# Analog_Drum.net
KiCad netlist of a schematic drawn in EAGLE
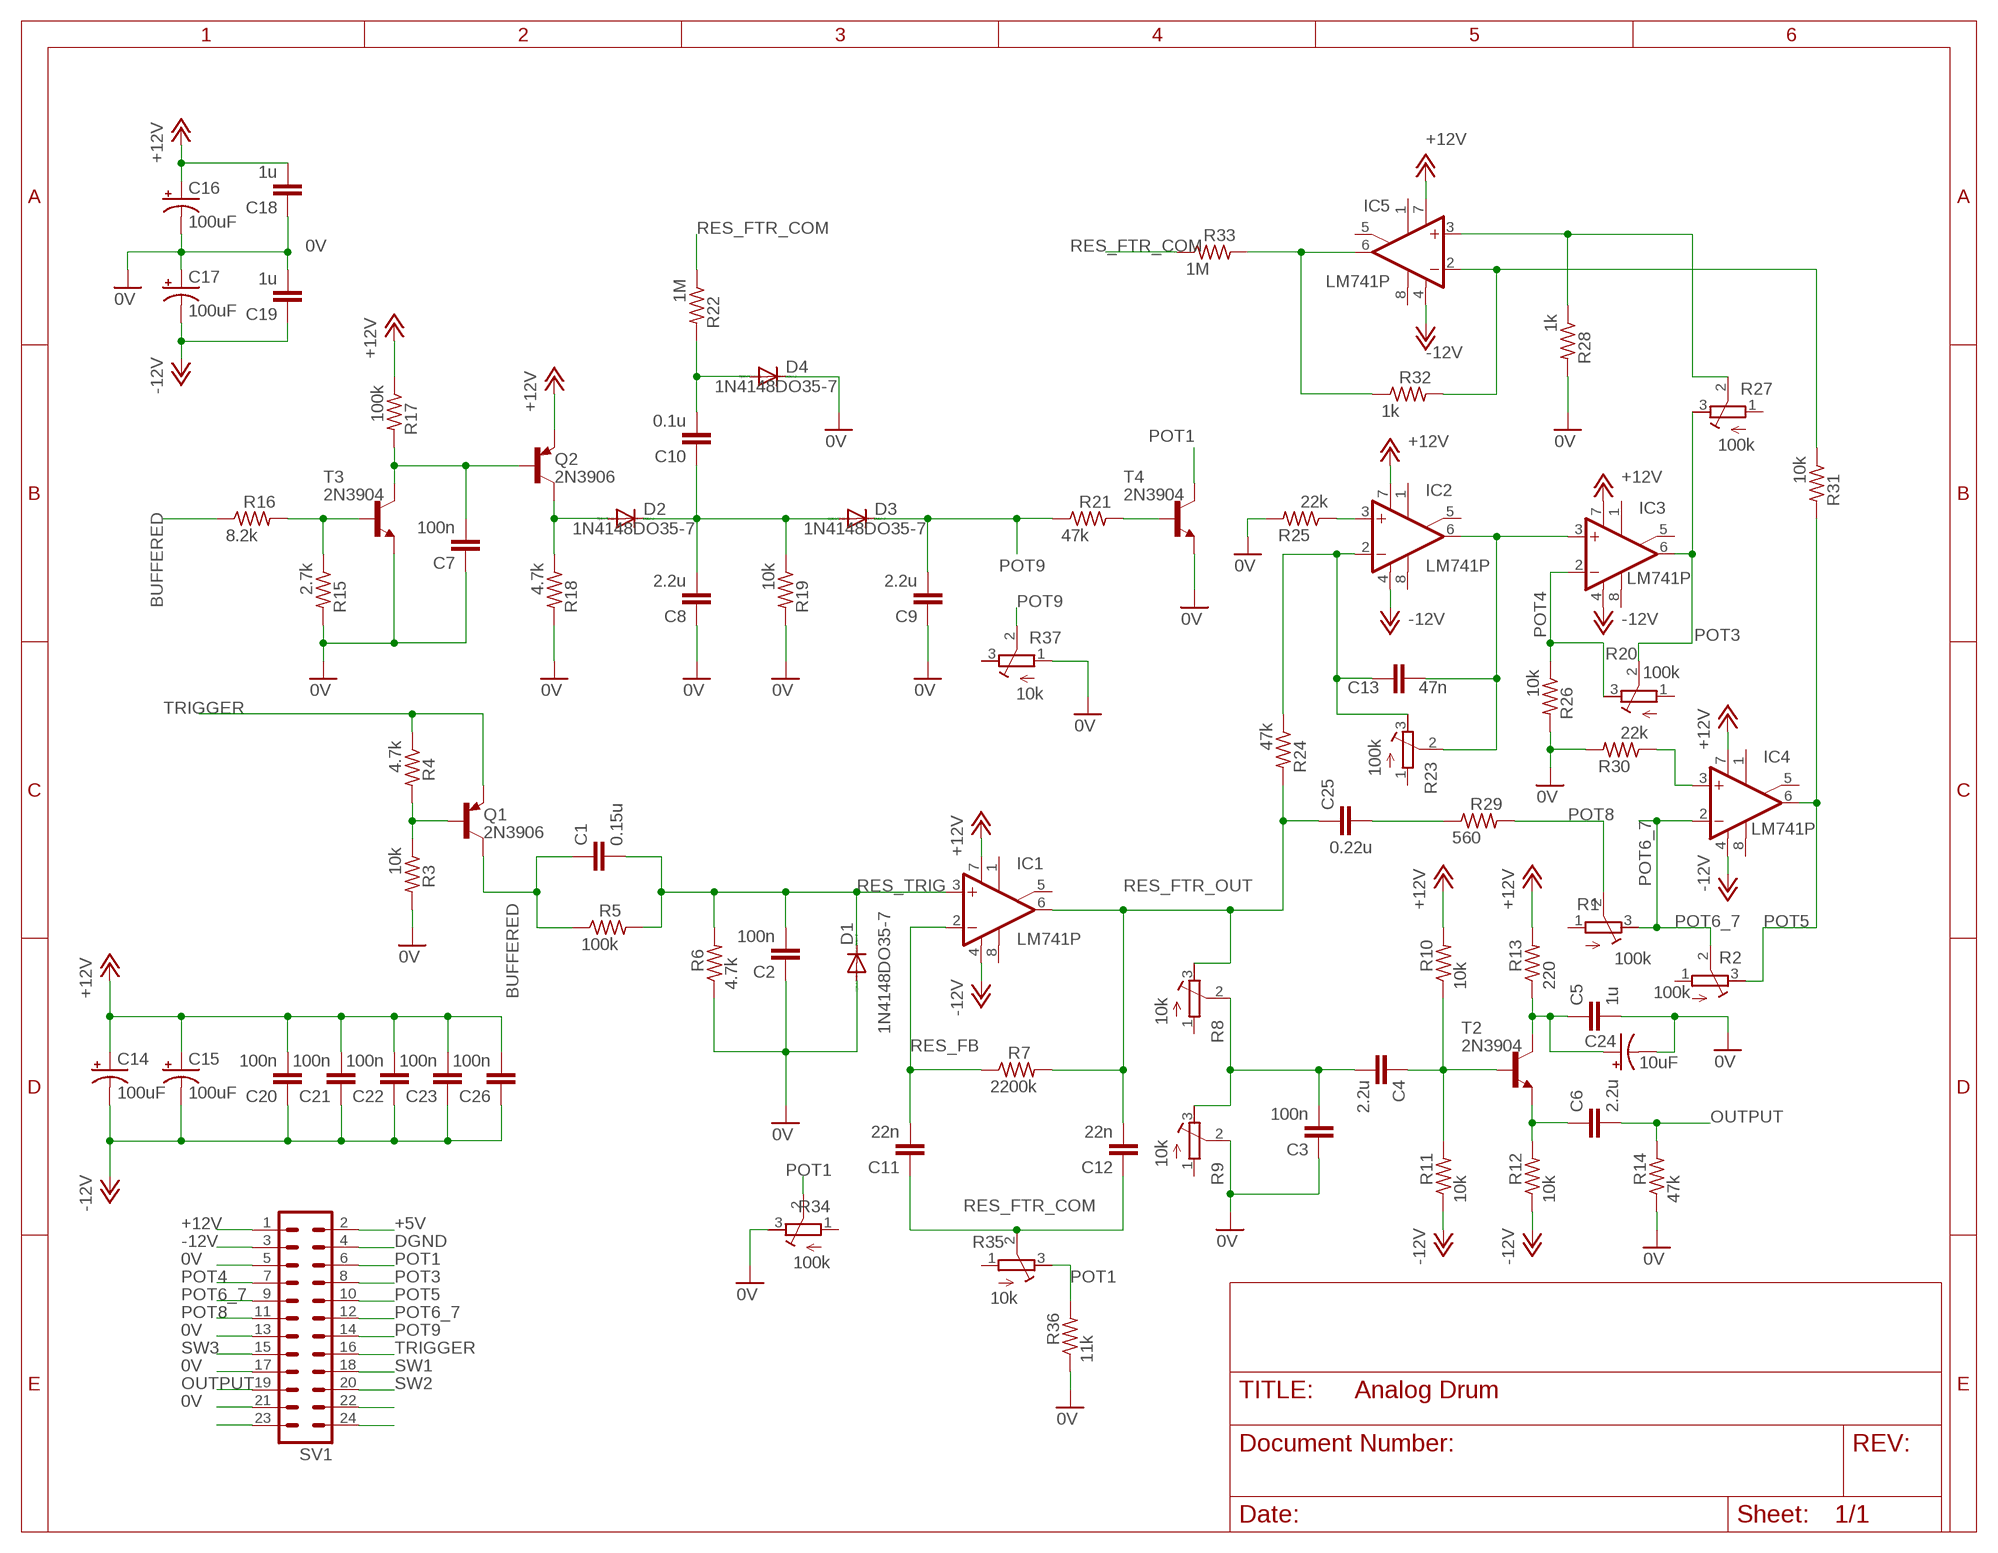
[diagram p0: schematic, sheet 1]

(export (version "E")
  (design (tool "Eeschema 10.0.6"))
  (components
    (comp (ref "C1")
      (value "0.15u")
      (footprint "eagle-import:C050-024X044")
      (libsource (lib "eagle-import") (part "C-EU050-024X044"))
    )
    (comp (ref "C2")
      (value "100n")
      (footprint "eagle-import:C050-024X044")
      (libsource (lib "eagle-import") (part "C-EU050-024X044"))
    )
    (comp (ref "C3")
      (value "100n")
      (footprint "eagle-import:C050-024X044")
      (libsource (lib "eagle-import") (part "C-EU050-024X044"))
    )
    (comp (ref "C4")
      (value "2.2u")
      (footprint "eagle-import:C050-024X044")
      (libsource (lib "eagle-import") (part "C-EU050-024X044"))
    )
    (comp (ref "C5")
      (value "1u")
      (footprint "eagle-import:C050-024X044")
      (libsource (lib "eagle-import") (part "C-EU050-024X044"))
    )
    (comp (ref "C6")
      (value "2.2u")
      (footprint "eagle-import:C050-024X044")
      (libsource (lib "eagle-import") (part "C-EU050-024X044"))
    )
    (comp (ref "C7")
      (value "100n")
      (footprint "eagle-import:C050-024X044")
      (libsource (lib "eagle-import") (part "C-EU050-024X044"))
    )
    (comp (ref "C8")
      (value "2.2u")
      (footprint "eagle-import:C050-024X044")
      (libsource (lib "eagle-import") (part "C-EU050-024X044"))
    )
    (comp (ref "C9")
      (value "2.2u")
      (footprint "eagle-import:C050-024X044")
      (libsource (lib "eagle-import") (part "C-EU050-024X044"))
    )
    (comp (ref "C10")
      (value "0.1u")
      (footprint "eagle-import:C050-024X044")
      (libsource (lib "eagle-import") (part "C-EU050-024X044"))
    )
    (comp (ref "C11")
      (value "22n")
      (footprint "eagle-import:C050-024X044")
      (libsource (lib "eagle-import") (part "C-EU050-024X044"))
    )
    (comp (ref "C12")
      (value "22n")
      (footprint "eagle-import:C050-024X044")
      (libsource (lib "eagle-import") (part "C-EU050-024X044"))
    )
    (comp (ref "C13")
      (value "47n")
      (footprint "eagle-import:C050-024X044")
      (libsource (lib "eagle-import") (part "C-EU050-024X044"))
    )
    (comp (ref "C14")
      (value "100uF")
      (footprint "eagle-import:E5-8,5")
      (libsource (lib "eagle-import") (part "CPOL-USE5-8.5"))
    )
    (comp (ref "C15")
      (value "100uF")
      (footprint "eagle-import:E5-8,5")
      (libsource (lib "eagle-import") (part "CPOL-USE5-8.5"))
    )
    (comp (ref "C16")
      (value "100uF")
      (footprint "eagle-import:E5-8,5")
      (libsource (lib "eagle-import") (part "CPOL-USE5-8.5"))
    )
    (comp (ref "C17")
      (value "100uF")
      (footprint "eagle-import:E5-8,5")
      (libsource (lib "eagle-import") (part "CPOL-USE5-8.5"))
    )
    (comp (ref "C18")
      (value "1u")
      (footprint "eagle-import:C050-024X044")
      (libsource (lib "eagle-import") (part "C-EU050-024X044"))
    )
    (comp (ref "C19")
      (value "1u")
      (footprint "eagle-import:C050-024X044")
      (libsource (lib "eagle-import") (part "C-EU050-024X044"))
    )
    (comp (ref "C20")
      (value "100n")
      (footprint "eagle-import:C050-024X044")
      (libsource (lib "eagle-import") (part "C-EU050-024X044"))
    )
    (comp (ref "C21")
      (value "100n")
      (footprint "eagle-import:C050-024X044")
      (libsource (lib "eagle-import") (part "C-EU050-024X044"))
    )
    (comp (ref "C22")
      (value "100n")
      (footprint "eagle-import:C050-024X044")
      (libsource (lib "eagle-import") (part "C-EU050-024X044"))
    )
    (comp (ref "C23")
      (value "100n")
      (footprint "eagle-import:C050-024X044")
      (libsource (lib "eagle-import") (part "C-EU050-024X044"))
    )
    (comp (ref "C24")
      (value "10uF")
      (footprint "eagle-import:E2,5-6")
      (libsource (lib "eagle-import") (part "CPOL-USE2.5-6"))
    )
    (comp (ref "C25")
      (value "0.22u")
      (footprint "eagle-import:C050-024X044")
      (libsource (lib "eagle-import") (part "C-EU050-024X044"))
    )
    (comp (ref "C26")
      (value "100n")
      (footprint "eagle-import:C050-024X044")
      (libsource (lib "eagle-import") (part "C-EU050-024X044"))
    )
    (comp (ref "D1")
      (value "1N4148DO35-7")
      (footprint "eagle-import:DO35-7")
      (libsource (lib "eagle-import") (part "1N4148DO35-7"))
    )
    (comp (ref "D2")
      (value "1N4148DO35-7")
      (footprint "eagle-import:DO35-7")
      (libsource (lib "eagle-import") (part "1N4148DO35-7"))
    )
    (comp (ref "D3")
      (value "1N4148DO35-7")
      (footprint "eagle-import:DO35-7")
      (libsource (lib "eagle-import") (part "1N4148DO35-7"))
    )
    (comp (ref "D4")
      (value "1N4148DO35-7")
      (footprint "eagle-import:DO35-7")
      (libsource (lib "eagle-import") (part "1N4148DO35-7"))
    )
    (comp (ref "IC1")
      (value "LM741P")
      (footprint "eagle-import:DIL08")
      (libsource (lib "eagle-import") (part "741PLM"))
    )
    (comp (ref "IC2")
      (value "LM741P")
      (footprint "eagle-import:DIL08")
      (libsource (lib "eagle-import") (part "741PLM"))
    )
    (comp (ref "IC3")
      (value "LM741P")
      (footprint "eagle-import:DIL08")
      (libsource (lib "eagle-import") (part "741PLM"))
    )
    (comp (ref "IC4")
      (value "LM741P")
      (footprint "eagle-import:DIL08")
      (libsource (lib "eagle-import") (part "741PLM"))
    )
    (comp (ref "IC5")
      (value "LM741P")
      (footprint "eagle-import:DIL08")
      (libsource (lib "eagle-import") (part "741PLM"))
    )
    (comp (ref "Q1")
      (value "2N3906")
      (footprint "eagle-import:TO92")
      (libsource (lib "eagle-import") (part "2N3906"))
    )
    (comp (ref "Q2")
      (value "2N3906")
      (footprint "eagle-import:TO92")
      (libsource (lib "eagle-import") (part "2N3906"))
    )
    (comp (ref "R1")
      (value "100k")
      (footprint "eagle-import:RTRIM64W")
      (libsource (lib "eagle-import") (part "R-TRIMM64W"))
    )
    (comp (ref "R2")
      (value "100k")
      (footprint "eagle-import:RTRIM64W")
      (libsource (lib "eagle-import") (part "R-TRIMM64W"))
    )
    (comp (ref "R3")
      (value "10k")
      (footprint "eagle-import:0207_10")
      (libsource (lib "eagle-import") (part "R-US_0207/10"))
    )
    (comp (ref "R4")
      (value "4.7k")
      (footprint "eagle-import:0207_10")
      (libsource (lib "eagle-import") (part "R-US_0207/10"))
    )
    (comp (ref "R5")
      (value "100k")
      (footprint "eagle-import:0207_10")
      (libsource (lib "eagle-import") (part "R-US_0207/10"))
    )
    (comp (ref "R6")
      (value "4.7k")
      (footprint "eagle-import:0207_10")
      (libsource (lib "eagle-import") (part "R-US_0207/10"))
    )
    (comp (ref "R7")
      (value "2200k")
      (footprint "eagle-import:0207_10")
      (libsource (lib "eagle-import") (part "R-US_0207/10"))
    )
    (comp (ref "R8")
      (value "10k")
      (footprint "eagle-import:RTRIM64W")
      (libsource (lib "eagle-import") (part "R-TRIMM64W"))
    )
    (comp (ref "R9")
      (value "10k")
      (footprint "eagle-import:RTRIM64W")
      (libsource (lib "eagle-import") (part "R-TRIMM64W"))
    )
    (comp (ref "R10")
      (value "10k")
      (footprint "eagle-import:0207_10")
      (libsource (lib "eagle-import") (part "R-US_0207/10"))
    )
    (comp (ref "R11")
      (value "10k")
      (footprint "eagle-import:0207_10")
      (libsource (lib "eagle-import") (part "R-US_0207/10"))
    )
    (comp (ref "R12")
      (value "10k")
      (footprint "eagle-import:0207_10")
      (libsource (lib "eagle-import") (part "R-US_0207/10"))
    )
    (comp (ref "R13")
      (value "220")
      (footprint "eagle-import:0207_10")
      (libsource (lib "eagle-import") (part "R-US_0207/10"))
    )
    (comp (ref "R14")
      (value "47k")
      (footprint "eagle-import:0207_10")
      (libsource (lib "eagle-import") (part "R-US_0207/10"))
    )
    (comp (ref "R15")
      (value "2.7k")
      (footprint "eagle-import:0207_10")
      (libsource (lib "eagle-import") (part "R-US_0207/10"))
    )
    (comp (ref "R16")
      (value "8.2k")
      (footprint "eagle-import:0207_10")
      (libsource (lib "eagle-import") (part "R-US_0207/10"))
    )
    (comp (ref "R17")
      (value "100k")
      (footprint "eagle-import:0207_10")
      (libsource (lib "eagle-import") (part "R-US_0207/10"))
    )
    (comp (ref "R18")
      (value "4.7k")
      (footprint "eagle-import:0207_10")
      (libsource (lib "eagle-import") (part "R-US_0207/10"))
    )
    (comp (ref "R19")
      (value "10k")
      (footprint "eagle-import:0207_10")
      (libsource (lib "eagle-import") (part "R-US_0207/10"))
    )
    (comp (ref "R20")
      (value "100k")
      (footprint "eagle-import:RTRIM64W")
      (libsource (lib "eagle-import") (part "R-TRIMM64W"))
    )
    (comp (ref "R21")
      (value "47k")
      (footprint "eagle-import:0207_10")
      (libsource (lib "eagle-import") (part "R-US_0207/10"))
    )
    (comp (ref "R22")
      (value "1M")
      (footprint "eagle-import:0207_10")
      (libsource (lib "eagle-import") (part "R-US_0207/10"))
    )
    (comp (ref "R23")
      (value "100k")
      (footprint "eagle-import:RTRIM64W")
      (libsource (lib "eagle-import") (part "R-TRIMM64W"))
    )
    (comp (ref "R24")
      (value "47k")
      (footprint "eagle-import:0207_10")
      (libsource (lib "eagle-import") (part "R-US_0207/10"))
    )
    (comp (ref "R25")
      (value "22k")
      (footprint "eagle-import:0207_10")
      (libsource (lib "eagle-import") (part "R-US_0207/10"))
    )
    (comp (ref "R26")
      (value "10k")
      (footprint "eagle-import:0207_10")
      (libsource (lib "eagle-import") (part "R-US_0207/10"))
    )
    (comp (ref "R27")
      (value "100k")
      (footprint "eagle-import:RTRIM64W")
      (libsource (lib "eagle-import") (part "R-TRIMM64W"))
    )
    (comp (ref "R28")
      (value "1k")
      (footprint "eagle-import:0207_10")
      (libsource (lib "eagle-import") (part "R-US_0207/10"))
    )
    (comp (ref "R29")
      (value "560")
      (footprint "eagle-import:0207_10")
      (libsource (lib "eagle-import") (part "R-US_0207/10"))
    )
    (comp (ref "R30")
      (value "22k")
      (footprint "eagle-import:0207_10")
      (libsource (lib "eagle-import") (part "R-US_0207/10"))
    )
    (comp (ref "R31")
      (value "10k")
      (footprint "eagle-import:0207_10")
      (libsource (lib "eagle-import") (part "R-US_0207/10"))
    )
    (comp (ref "R32")
      (value "1k")
      (footprint "eagle-import:0207_10")
      (libsource (lib "eagle-import") (part "R-US_0207/10"))
    )
    (comp (ref "R33")
      (value "1M")
      (footprint "eagle-import:0207_10")
      (libsource (lib "eagle-import") (part "R-US_0207/10"))
    )
    (comp (ref "R34")
      (value "100k")
      (footprint "eagle-import:RTRIM64W")
      (libsource (lib "eagle-import") (part "R-TRIMM64W"))
    )
    (comp (ref "R35")
      (value "10k")
      (footprint "eagle-import:RTRIM64W")
      (libsource (lib "eagle-import") (part "R-TRIMM64W"))
    )
    (comp (ref "R36")
      (value "11k")
      (footprint "eagle-import:0207_10")
      (libsource (lib "eagle-import") (part "R-US_0207/10"))
    )
    (comp (ref "R37")
      (value "10k")
      (footprint "eagle-import:RTRIM64W")
      (libsource (lib "eagle-import") (part "R-TRIMM64W"))
    )
    (comp (ref "SV1")
      (value "MA12-2")
      (footprint "eagle-import:MA12-2")
      (libsource (lib "eagle-import") (part "MA12-2"))
    )
    (comp (ref "T2")
      (value "2N3904")
      (footprint "eagle-import:TO92")
      (libsource (lib "eagle-import") (part "2N3904"))
    )
    (comp (ref "T3")
      (value "2N3904")
      (footprint "eagle-import:TO92")
      (libsource (lib "eagle-import") (part "2N3904"))
    )
    (comp (ref "T4")
      (value "2N3904")
      (footprint "eagle-import:TO92")
      (libsource (lib "eagle-import") (part "2N3904"))
    )
  )
  (nets
    (net (code "1") (name "+12V") (class "Default")
      (node (ref "C14") (pin "+") (pinfunction "+_+") (pintype "passive"))
      (node (ref "C15") (pin "+") (pinfunction "+_+") (pintype "passive"))
      (node (ref "C16") (pin "+") (pinfunction "+_+") (pintype "passive"))
      (node (ref "C18") (pin "2") (pinfunction "2_2") (pintype "passive"))
      (node (ref "C20") (pin "2") (pinfunction "2_2") (pintype "passive"))
      (node (ref "C21") (pin "2") (pinfunction "2_2") (pintype "passive"))
      (node (ref "C22") (pin "2") (pinfunction "2_2") (pintype "passive"))
      (node (ref "C23") (pin "2") (pinfunction "2_2") (pintype "passive"))
      (node (ref "C26") (pin "2") (pinfunction "2_2") (pintype "passive"))
      (node (ref "IC1") (pin "7") (pinfunction "V+_7") (pintype "power_in"))
      (node (ref "IC2") (pin "7") (pinfunction "V+_7") (pintype "power_in"))
      (node (ref "IC3") (pin "7") (pinfunction "V+_7") (pintype "power_in"))
      (node (ref "IC4") (pin "7") (pinfunction "V+_7") (pintype "power_in"))
      (node (ref "IC5") (pin "7") (pinfunction "V+_7") (pintype "power_in"))
      (node (ref "Q2") (pin "3") (pinfunction "E_3") (pintype "passive"))
      (node (ref "R10") (pin "2") (pinfunction "2_2") (pintype "passive"))
      (node (ref "R13") (pin "2") (pinfunction "2_2") (pintype "passive"))
      (node (ref "R17") (pin "1") (pinfunction "1_1") (pintype "passive"))
      (node (ref "SV1") (pin "1") (pinfunction "1_1") (pintype "passive"))
    )
    (net (code "2") (name "-12V") (class "Default")
      (node (ref "C14") (pin "-") (pinfunction "-_-") (pintype "passive"))
      (node (ref "C15") (pin "-") (pinfunction "-_-") (pintype "passive"))
      (node (ref "C17") (pin "-") (pinfunction "-_-") (pintype "passive"))
      (node (ref "C19") (pin "1") (pinfunction "1_1") (pintype "passive"))
      (node (ref "C20") (pin "1") (pinfunction "1_1") (pintype "passive"))
      (node (ref "C21") (pin "1") (pinfunction "1_1") (pintype "passive"))
      (node (ref "C22") (pin "1") (pinfunction "1_1") (pintype "passive"))
      (node (ref "C23") (pin "1") (pinfunction "1_1") (pintype "passive"))
      (node (ref "C26") (pin "1") (pinfunction "1_1") (pintype "passive"))
      (node (ref "IC1") (pin "4") (pinfunction "V-_4") (pintype "power_in"))
      (node (ref "IC2") (pin "4") (pinfunction "V-_4") (pintype "power_in"))
      (node (ref "IC3") (pin "4") (pinfunction "V-_4") (pintype "power_in"))
      (node (ref "IC4") (pin "4") (pinfunction "V-_4") (pintype "power_in"))
      (node (ref "IC5") (pin "4") (pinfunction "V-_4") (pintype "power_in"))
      (node (ref "R11") (pin "1") (pinfunction "1_1") (pintype "passive"))
      (node (ref "R12") (pin "1") (pinfunction "1_1") (pintype "passive"))
      (node (ref "SV1") (pin "3") (pinfunction "3_3") (pintype "passive"))
    )
    (net (code "3") (name "/+5V") (class "Default")
      (node (ref "SV1") (pin "2") (pinfunction "2_2") (pintype "passive"))
    )
    (net (code "4") (name "/BUFFERED") (class "Default")
      (node (ref "C1") (pin "1") (pinfunction "1_1") (pintype "passive"))
      (node (ref "Q1") (pin "1") (pinfunction "C_1") (pintype "passive"))
      (node (ref "R16") (pin "1") (pinfunction "1_1") (pintype "passive"))
      (node (ref "R5") (pin "1") (pinfunction "1_1") (pintype "passive"))
    )
    (net (code "5") (name "/DGND") (class "Default")
      (node (ref "SV1") (pin "4") (pinfunction "4_4") (pintype "passive"))
    )
    (net (code "6") (name "/OUTPUT") (class "Default")
      (node (ref "C6") (pin "2") (pinfunction "2_2") (pintype "passive"))
      (node (ref "R14") (pin "2") (pinfunction "2_2") (pintype "passive"))
      (node (ref "SV1") (pin "19") (pinfunction "19_19") (pintype "passive"))
    )
    (net (code "7") (name "/POT1") (class "Default")
      (node (ref "R34") (pin "2") (pinfunction "S_2") (pintype "passive"))
      (node (ref "R35") (pin "3") (pinfunction "E_3") (pintype "passive"))
      (node (ref "R36") (pin "2") (pinfunction "2_2") (pintype "passive"))
      (node (ref "SV1") (pin "6") (pinfunction "6_6") (pintype "passive"))
      (node (ref "T4") (pin "1") (pinfunction "C_1") (pintype "passive"))
    )
    (net (code "8") (name "/POT3") (class "Default")
      (node (ref "IC3") (pin "6") (pinfunction "OUT_6") (pintype "output"))
      (node (ref "R20") (pin "2") (pinfunction "S_2") (pintype "passive"))
      (node (ref "R27") (pin "3") (pinfunction "E_3") (pintype "passive"))
      (node (ref "SV1") (pin "8") (pinfunction "8_8") (pintype "passive"))
    )
    (net (code "9") (name "/POT4") (class "Default")
      (node (ref "IC3") (pin "2") (pinfunction "-IN_2") (pintype "input"))
      (node (ref "R20") (pin "3") (pinfunction "E_3") (pintype "passive"))
      (node (ref "R26") (pin "1") (pinfunction "1_1") (pintype "passive"))
      (node (ref "SV1") (pin "7") (pinfunction "7_7") (pintype "passive"))
    )
    (net (code "10") (name "/POT5") (class "Default")
      (node (ref "IC4") (pin "6") (pinfunction "OUT_6") (pintype "output"))
      (node (ref "R2") (pin "3") (pinfunction "E_3") (pintype "passive"))
      (node (ref "R31") (pin "2") (pinfunction "2_2") (pintype "passive"))
      (node (ref "SV1") (pin "10") (pinfunction "10_10") (pintype "passive"))
    )
    (net (code "11") (name "/POT6_7") (class "Default")
      (node (ref "IC4") (pin "2") (pinfunction "-IN_2") (pintype "input"))
      (node (ref "R1") (pin "3") (pinfunction "E_3") (pintype "passive"))
      (node (ref "R2") (pin "2") (pinfunction "S_2") (pintype "passive"))
      (node (ref "SV1") (pin "12") (pinfunction "12_12") (pintype "passive"))
      (node (ref "SV1") (pin "9") (pinfunction "9_9") (pintype "passive"))
    )
    (net (code "12") (name "/POT8") (class "Default")
      (node (ref "R1") (pin "2") (pinfunction "S_2") (pintype "passive"))
      (node (ref "R29") (pin "2") (pinfunction "2_2") (pintype "passive"))
      (node (ref "SV1") (pin "11") (pinfunction "11_11") (pintype "passive"))
    )
    (net (code "13") (name "/POT9") (class "Default")
      (node (ref "C9") (pin "2") (pinfunction "2_2") (pintype "passive"))
      (node (ref "D3") (pin "C") (pinfunction "C_C") (pintype "passive"))
      (node (ref "R21") (pin "1") (pinfunction "1_1") (pintype "passive"))
      (node (ref "R37") (pin "2") (pinfunction "S_2") (pintype "passive"))
      (node (ref "SV1") (pin "14") (pinfunction "14_14") (pintype "passive"))
    )
    (net (code "14") (name "/RES_FB") (class "Default")
      (node (ref "C11") (pin "2") (pinfunction "2_2") (pintype "passive"))
      (node (ref "IC1") (pin "2") (pinfunction "-IN_2") (pintype "input"))
      (node (ref "R7") (pin "1") (pinfunction "1_1") (pintype "passive"))
    )
    (net (code "15") (name "/RES_FTR_COM") (class "Default")
      (node (ref "C11") (pin "1") (pinfunction "1_1") (pintype "passive"))
      (node (ref "C12") (pin "1") (pinfunction "1_1") (pintype "passive"))
      (node (ref "R22") (pin "1") (pinfunction "1_1") (pintype "passive"))
      (node (ref "R33") (pin "1") (pinfunction "1_1") (pintype "passive"))
      (node (ref "R35") (pin "2") (pinfunction "S_2") (pintype "passive"))
    )
    (net (code "16") (name "/RES_FTR_OUT") (class "Default")
      (node (ref "C12") (pin "2") (pinfunction "2_2") (pintype "passive"))
      (node (ref "C25") (pin "1") (pinfunction "1_1") (pintype "passive"))
      (node (ref "IC1") (pin "6") (pinfunction "OUT_6") (pintype "output"))
      (node (ref "R24") (pin "2") (pinfunction "2_2") (pintype "passive"))
      (node (ref "R7") (pin "2") (pinfunction "2_2") (pintype "passive"))
      (node (ref "R8") (pin "3") (pinfunction "E_3") (pintype "passive"))
    )
    (net (code "17") (name "/RES_TRIG") (class "Default")
      (node (ref "C1") (pin "2") (pinfunction "2_2") (pintype "passive"))
      (node (ref "C2") (pin "2") (pinfunction "2_2") (pintype "passive"))
      (node (ref "D1") (pin "C") (pinfunction "C_C") (pintype "passive"))
      (node (ref "IC1") (pin "3") (pinfunction "+IN_3") (pintype "input"))
      (node (ref "R5") (pin "2") (pinfunction "2_2") (pintype "passive"))
      (node (ref "R6") (pin "2") (pinfunction "2_2") (pintype "passive"))
    )
    (net (code "18") (name "/SW1") (class "Default")
      (node (ref "SV1") (pin "18") (pinfunction "18_18") (pintype "passive"))
    )
    (net (code "19") (name "/SW2") (class "Default")
      (node (ref "SV1") (pin "20") (pinfunction "20_20") (pintype "passive"))
    )
    (net (code "20") (name "/SW3") (class "Default")
      (node (ref "SV1") (pin "15") (pinfunction "15_15") (pintype "passive"))
    )
    (net (code "21") (name "/TRIGGER") (class "Default")
      (node (ref "Q1") (pin "3") (pinfunction "E_3") (pintype "passive"))
      (node (ref "R4") (pin "1") (pinfunction "1_1") (pintype "passive"))
      (node (ref "SV1") (pin "16") (pinfunction "16_16") (pintype "passive"))
    )
    (net (code "22") (name "0V") (class "Default")
      (node (ref "C16") (pin "-") (pinfunction "-_-") (pintype "passive"))
      (node (ref "C17") (pin "+") (pinfunction "+_+") (pintype "passive"))
      (node (ref "C18") (pin "1") (pinfunction "1_1") (pintype "passive"))
      (node (ref "C19") (pin "2") (pinfunction "2_2") (pintype "passive"))
      (node (ref "C2") (pin "1") (pinfunction "1_1") (pintype "passive"))
      (node (ref "C24") (pin "-") (pinfunction "-_-") (pintype "passive"))
      (node (ref "C3") (pin "1") (pinfunction "1_1") (pintype "passive"))
      (node (ref "C5") (pin "2") (pinfunction "2_2") (pintype "passive"))
      (node (ref "C7") (pin "1") (pinfunction "1_1") (pintype "passive"))
      (node (ref "C8") (pin "1") (pinfunction "1_1") (pintype "passive"))
      (node (ref "C9") (pin "1") (pinfunction "1_1") (pintype "passive"))
      (node (ref "D1") (pin "A") (pinfunction "A_A") (pintype "passive"))
      (node (ref "D4") (pin "C") (pinfunction "C_C") (pintype "passive"))
      (node (ref "R14") (pin "1") (pinfunction "1_1") (pintype "passive"))
      (node (ref "R15") (pin "2") (pinfunction "2_2") (pintype "passive"))
      (node (ref "R18") (pin "2") (pinfunction "2_2") (pintype "passive"))
      (node (ref "R19") (pin "2") (pinfunction "2_2") (pintype "passive"))
      (node (ref "R25") (pin "2") (pinfunction "2_2") (pintype "passive"))
      (node (ref "R26") (pin "2") (pinfunction "2_2") (pintype "passive"))
      (node (ref "R28") (pin "2") (pinfunction "2_2") (pintype "passive"))
      (node (ref "R3") (pin "2") (pinfunction "2_2") (pintype "passive"))
      (node (ref "R30") (pin "2") (pinfunction "2_2") (pintype "passive"))
      (node (ref "R34") (pin "3") (pinfunction "E_3") (pintype "passive"))
      (node (ref "R36") (pin "1") (pinfunction "1_1") (pintype "passive"))
      (node (ref "R37") (pin "1") (pinfunction "A_1") (pintype "passive"))
      (node (ref "R6") (pin "1") (pinfunction "1_1") (pintype "passive"))
      (node (ref "R9") (pin "2") (pinfunction "S_2") (pintype "passive"))
      (node (ref "SV1") (pin "13") (pinfunction "13_13") (pintype "passive"))
      (node (ref "SV1") (pin "17") (pinfunction "17_17") (pintype "passive"))
      (node (ref "SV1") (pin "21") (pinfunction "21_21") (pintype "passive"))
      (node (ref "SV1") (pin "5") (pinfunction "5_5") (pintype "passive"))
      (node (ref "T3") (pin "3") (pinfunction "E_3") (pintype "passive"))
      (node (ref "T4") (pin "3") (pinfunction "E_3") (pintype "passive"))
    )
    (net (code "23") (name "Net-(C10-Pad1)") (class "Default")
      (node (ref "C10") (pin "1") (pinfunction "1_1") (pintype "passive"))
      (node (ref "C8") (pin "2") (pinfunction "2_2") (pintype "passive"))
      (node (ref "D2") (pin "C") (pinfunction "C_C") (pintype "passive"))
      (node (ref "D3") (pin "A") (pinfunction "A_A") (pintype "passive"))
      (node (ref "R19") (pin "1") (pinfunction "1_1") (pintype "passive"))
    )
    (net (code "24") (name "Net-(C10-Pad2)") (class "Default")
      (node (ref "C10") (pin "2") (pinfunction "2_2") (pintype "passive"))
      (node (ref "D4") (pin "A") (pinfunction "A_A") (pintype "passive"))
      (node (ref "R22") (pin "2") (pinfunction "2_2") (pintype "passive"))
    )
    (net (code "25") (name "Net-(C25-Pad2)") (class "Default")
      (node (ref "C25") (pin "2") (pinfunction "2_2") (pintype "passive"))
      (node (ref "R29") (pin "1") (pinfunction "1_1") (pintype "passive"))
    )
    (net (code "26") (name "Net-(IC2-+IN)") (class "Default")
      (node (ref "IC2") (pin "3") (pinfunction "+IN_3") (pintype "input"))
      (node (ref "R25") (pin "1") (pinfunction "1_1") (pintype "passive"))
    )
    (net (code "27") (name "Net-(IC2--IN)") (class "Default")
      (node (ref "C13") (pin "2") (pinfunction "2_2") (pintype "passive"))
      (node (ref "IC2") (pin "2") (pinfunction "-IN_2") (pintype "input"))
      (node (ref "R23") (pin "3") (pinfunction "E_3") (pintype "passive"))
      (node (ref "R24") (pin "1") (pinfunction "1_1") (pintype "passive"))
    )
    (net (code "28") (name "Net-(IC2-OUT)") (class "Default")
      (node (ref "C13") (pin "1") (pinfunction "1_1") (pintype "passive"))
      (node (ref "IC2") (pin "6") (pinfunction "OUT_6") (pintype "output"))
      (node (ref "IC3") (pin "3") (pinfunction "+IN_3") (pintype "input"))
      (node (ref "R23") (pin "2") (pinfunction "S_2") (pintype "passive"))
    )
    (net (code "29") (name "Net-(IC4-+IN)") (class "Default")
      (node (ref "IC4") (pin "3") (pinfunction "+IN_3") (pintype "input"))
      (node (ref "R30") (pin "1") (pinfunction "1_1") (pintype "passive"))
    )
    (net (code "30") (name "Net-(IC5-+IN)") (class "Default")
      (node (ref "IC5") (pin "3") (pinfunction "+IN_3") (pintype "input"))
      (node (ref "R27") (pin "2") (pinfunction "S_2") (pintype "passive"))
      (node (ref "R28") (pin "1") (pinfunction "1_1") (pintype "passive"))
    )
    (net (code "31") (name "Net-(IC5--IN)") (class "Default")
      (node (ref "IC5") (pin "2") (pinfunction "-IN_2") (pintype "input"))
      (node (ref "R31") (pin "1") (pinfunction "1_1") (pintype "passive"))
      (node (ref "R32") (pin "2") (pinfunction "2_2") (pintype "passive"))
    )
    (net (code "32") (name "Net-(IC5-OUT)") (class "Default")
      (node (ref "IC5") (pin "6") (pinfunction "OUT_6") (pintype "output"))
      (node (ref "R32") (pin "1") (pinfunction "1_1") (pintype "passive"))
      (node (ref "R33") (pin "2") (pinfunction "2_2") (pintype "passive"))
    )
    (net (code "33") (name "Net-(Q1-B)") (class "Default")
      (node (ref "Q1") (pin "2") (pinfunction "B_2") (pintype "passive"))
      (node (ref "R3") (pin "1") (pinfunction "1_1") (pintype "passive"))
      (node (ref "R4") (pin "2") (pinfunction "2_2") (pintype "passive"))
    )
    (net (code "34") (name "Net-(Q2-B)") (class "Default")
      (node (ref "C7") (pin "2") (pinfunction "2_2") (pintype "passive"))
      (node (ref "Q2") (pin "2") (pinfunction "B_2") (pintype "passive"))
      (node (ref "R17") (pin "2") (pinfunction "2_2") (pintype "passive"))
      (node (ref "T3") (pin "1") (pinfunction "C_1") (pintype "passive"))
    )
    (net (code "35") (name "Net-(Q2-C)") (class "Default")
      (node (ref "D2") (pin "A") (pinfunction "A_A") (pintype "passive"))
      (node (ref "Q2") (pin "1") (pinfunction "C_1") (pintype "passive"))
      (node (ref "R18") (pin "1") (pinfunction "1_1") (pintype "passive"))
    )
    (net (code "36") (name "Net-(R8-S)") (class "Default")
      (node (ref "C3") (pin "2") (pinfunction "2_2") (pintype "passive"))
      (node (ref "C4") (pin "2") (pinfunction "2_2") (pintype "passive"))
      (node (ref "R8") (pin "2") (pinfunction "S_2") (pintype "passive"))
      (node (ref "R9") (pin "3") (pinfunction "E_3") (pintype "passive"))
    )
    (net (code "37") (name "Net-(T2-B)") (class "Default")
      (node (ref "C4") (pin "1") (pinfunction "1_1") (pintype "passive"))
      (node (ref "R10") (pin "1") (pinfunction "1_1") (pintype "passive"))
      (node (ref "R11") (pin "2") (pinfunction "2_2") (pintype "passive"))
      (node (ref "T2") (pin "2") (pinfunction "B_2") (pintype "passive"))
    )
    (net (code "38") (name "Net-(T2-C)") (class "Default")
      (node (ref "C24") (pin "+") (pinfunction "+_+") (pintype "passive"))
      (node (ref "C5") (pin "1") (pinfunction "1_1") (pintype "passive"))
      (node (ref "R13") (pin "1") (pinfunction "1_1") (pintype "passive"))
      (node (ref "T2") (pin "1") (pinfunction "C_1") (pintype "passive"))
    )
    (net (code "39") (name "Net-(T2-E)") (class "Default")
      (node (ref "C6") (pin "1") (pinfunction "1_1") (pintype "passive"))
      (node (ref "R12") (pin "2") (pinfunction "2_2") (pintype "passive"))
      (node (ref "T2") (pin "3") (pinfunction "E_3") (pintype "passive"))
    )
    (net (code "40") (name "Net-(T3-B)") (class "Default")
      (node (ref "R15") (pin "1") (pinfunction "1_1") (pintype "passive"))
      (node (ref "R16") (pin "2") (pinfunction "2_2") (pintype "passive"))
      (node (ref "T3") (pin "2") (pinfunction "B_2") (pintype "passive"))
    )
    (net (code "41") (name "Net-(T4-B)") (class "Default")
      (node (ref "R21") (pin "2") (pinfunction "2_2") (pintype "passive"))
      (node (ref "T4") (pin "2") (pinfunction "B_2") (pintype "passive"))
    )
    (net (code "42") (name "unconnected-(IC1-ON1-Pad1)") (class "Default")
      (node (ref "IC1") (pin "1") (pinfunction "ON1_1") (pintype "passive"))
    )
    (net (code "43") (name "unconnected-(IC1-ON2-Pad5)") (class "Default")
      (node (ref "IC1") (pin "5") (pinfunction "ON2_5") (pintype "passive"))
    )
    (net (code "44") (name "unconnected-(IC1-OPT-Pad8)") (class "Default")
      (node (ref "IC1") (pin "8") (pinfunction "OPT_8") (pintype "passive"))
    )
    (net (code "45") (name "unconnected-(IC2-ON1-Pad1)") (class "Default")
      (node (ref "IC2") (pin "1") (pinfunction "ON1_1") (pintype "passive"))
    )
    (net (code "46") (name "unconnected-(IC2-ON2-Pad5)") (class "Default")
      (node (ref "IC2") (pin "5") (pinfunction "ON2_5") (pintype "passive"))
    )
    (net (code "47") (name "unconnected-(IC2-OPT-Pad8)") (class "Default")
      (node (ref "IC2") (pin "8") (pinfunction "OPT_8") (pintype "passive"))
    )
    (net (code "48") (name "unconnected-(IC3-ON1-Pad1)") (class "Default")
      (node (ref "IC3") (pin "1") (pinfunction "ON1_1") (pintype "passive"))
    )
    (net (code "49") (name "unconnected-(IC3-ON2-Pad5)") (class "Default")
      (node (ref "IC3") (pin "5") (pinfunction "ON2_5") (pintype "passive"))
    )
    (net (code "50") (name "unconnected-(IC3-OPT-Pad8)") (class "Default")
      (node (ref "IC3") (pin "8") (pinfunction "OPT_8") (pintype "passive"))
    )
    (net (code "51") (name "unconnected-(IC4-ON1-Pad1)") (class "Default")
      (node (ref "IC4") (pin "1") (pinfunction "ON1_1") (pintype "passive"))
    )
    (net (code "52") (name "unconnected-(IC4-ON2-Pad5)") (class "Default")
      (node (ref "IC4") (pin "5") (pinfunction "ON2_5") (pintype "passive"))
    )
    (net (code "53") (name "unconnected-(IC4-OPT-Pad8)") (class "Default")
      (node (ref "IC4") (pin "8") (pinfunction "OPT_8") (pintype "passive"))
    )
    (net (code "54") (name "unconnected-(IC5-ON1-Pad1)") (class "Default")
      (node (ref "IC5") (pin "1") (pinfunction "ON1_1") (pintype "passive"))
    )
    (net (code "55") (name "unconnected-(IC5-ON2-Pad5)") (class "Default")
      (node (ref "IC5") (pin "5") (pinfunction "ON2_5") (pintype "passive"))
    )
    (net (code "56") (name "unconnected-(IC5-OPT-Pad8)") (class "Default")
      (node (ref "IC5") (pin "8") (pinfunction "OPT_8") (pintype "passive"))
    )
    (net (code "57") (name "unconnected-(R1-A-Pad1)") (class "Default")
      (node (ref "R1") (pin "1") (pinfunction "A_1") (pintype "passive"))
    )
    (net (code "58") (name "unconnected-(R2-A-Pad1)") (class "Default")
      (node (ref "R2") (pin "1") (pinfunction "A_1") (pintype "passive"))
    )
    (net (code "59") (name "unconnected-(R8-A-Pad1)") (class "Default")
      (node (ref "R8") (pin "1") (pinfunction "A_1") (pintype "passive"))
    )
    (net (code "60") (name "unconnected-(R9-A-Pad1)") (class "Default")
      (node (ref "R9") (pin "1") (pinfunction "A_1") (pintype "passive"))
    )
    (net (code "61") (name "unconnected-(R20-A-Pad1)") (class "Default")
      (node (ref "R20") (pin "1") (pinfunction "A_1") (pintype "passive"))
    )
    (net (code "62") (name "unconnected-(R23-A-Pad1)") (class "Default")
      (node (ref "R23") (pin "1") (pinfunction "A_1") (pintype "passive"))
    )
    (net (code "63") (name "unconnected-(R27-A-Pad1)") (class "Default")
      (node (ref "R27") (pin "1") (pinfunction "A_1") (pintype "passive"))
    )
    (net (code "64") (name "unconnected-(R34-A-Pad1)") (class "Default")
      (node (ref "R34") (pin "1") (pinfunction "A_1") (pintype "passive"))
    )
    (net (code "65") (name "unconnected-(R35-A-Pad1)") (class "Default")
      (node (ref "R35") (pin "1") (pinfunction "A_1") (pintype "passive"))
    )
    (net (code "66") (name "unconnected-(R37-E-Pad3)") (class "Default")
      (node (ref "R37") (pin "3") (pinfunction "E_3") (pintype "passive"))
    )
    (net (code "67") (name "unconnected-(SV1-Pad22)") (class "Default")
      (node (ref "SV1") (pin "22") (pinfunction "22_22") (pintype "passive"))
    )
    (net (code "68") (name "unconnected-(SV1-Pad23)") (class "Default")
      (node (ref "SV1") (pin "23") (pinfunction "23_23") (pintype "passive"))
    )
    (net (code "69") (name "unconnected-(SV1-Pad24)") (class "Default")
      (node (ref "SV1") (pin "24") (pinfunction "24_24") (pintype "passive"))
    )
  )
)
